# STM32F767ZI_eval_0.net
KiCad netlist of a schematic drawn in EAGLE
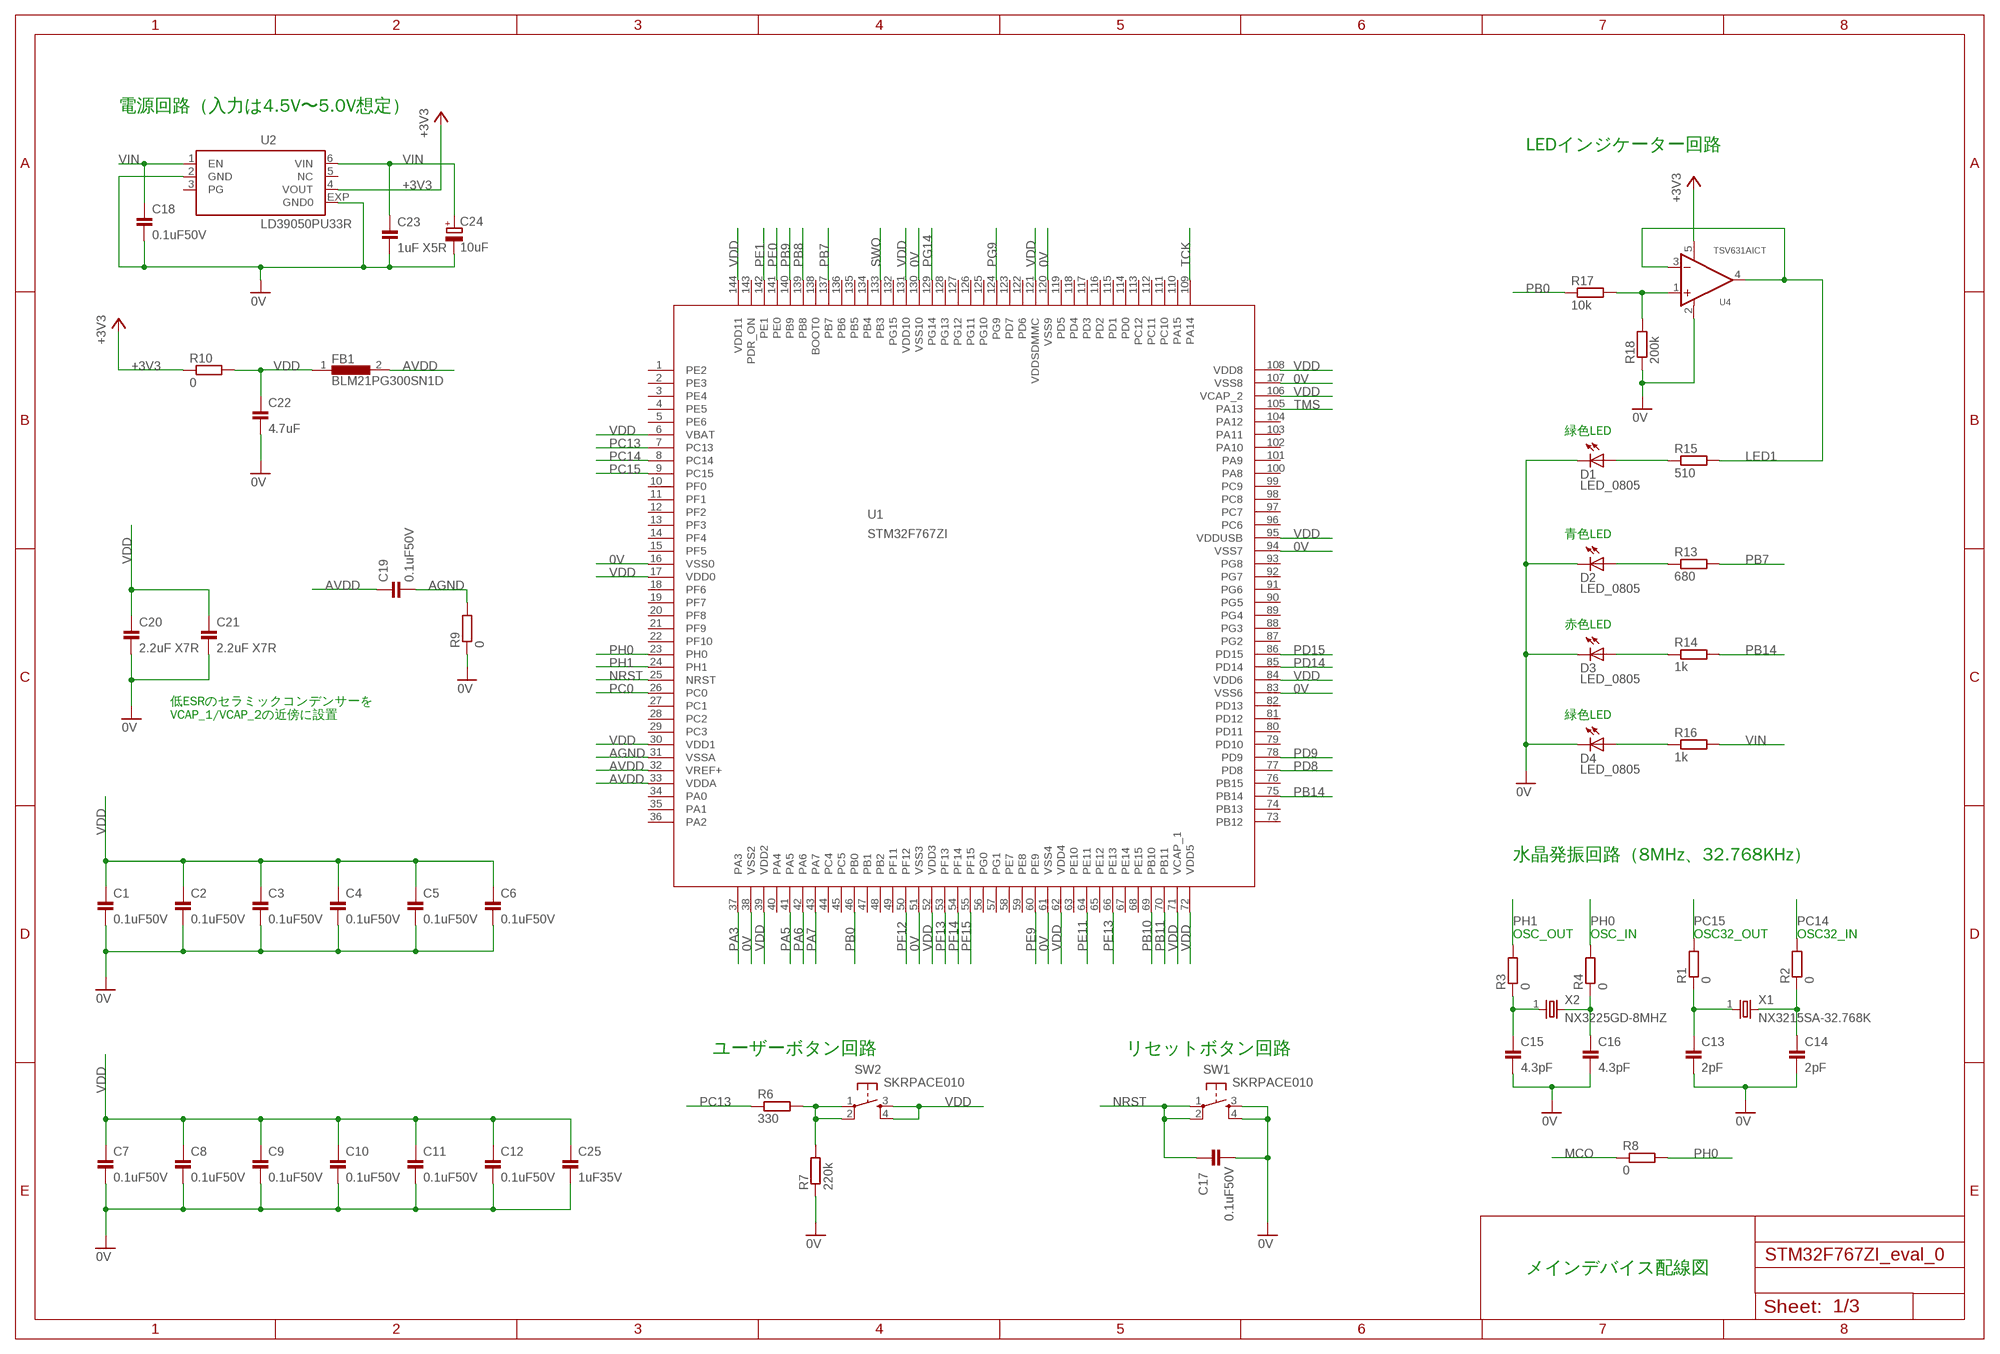
[diagram p0: schematic, sheet 1]
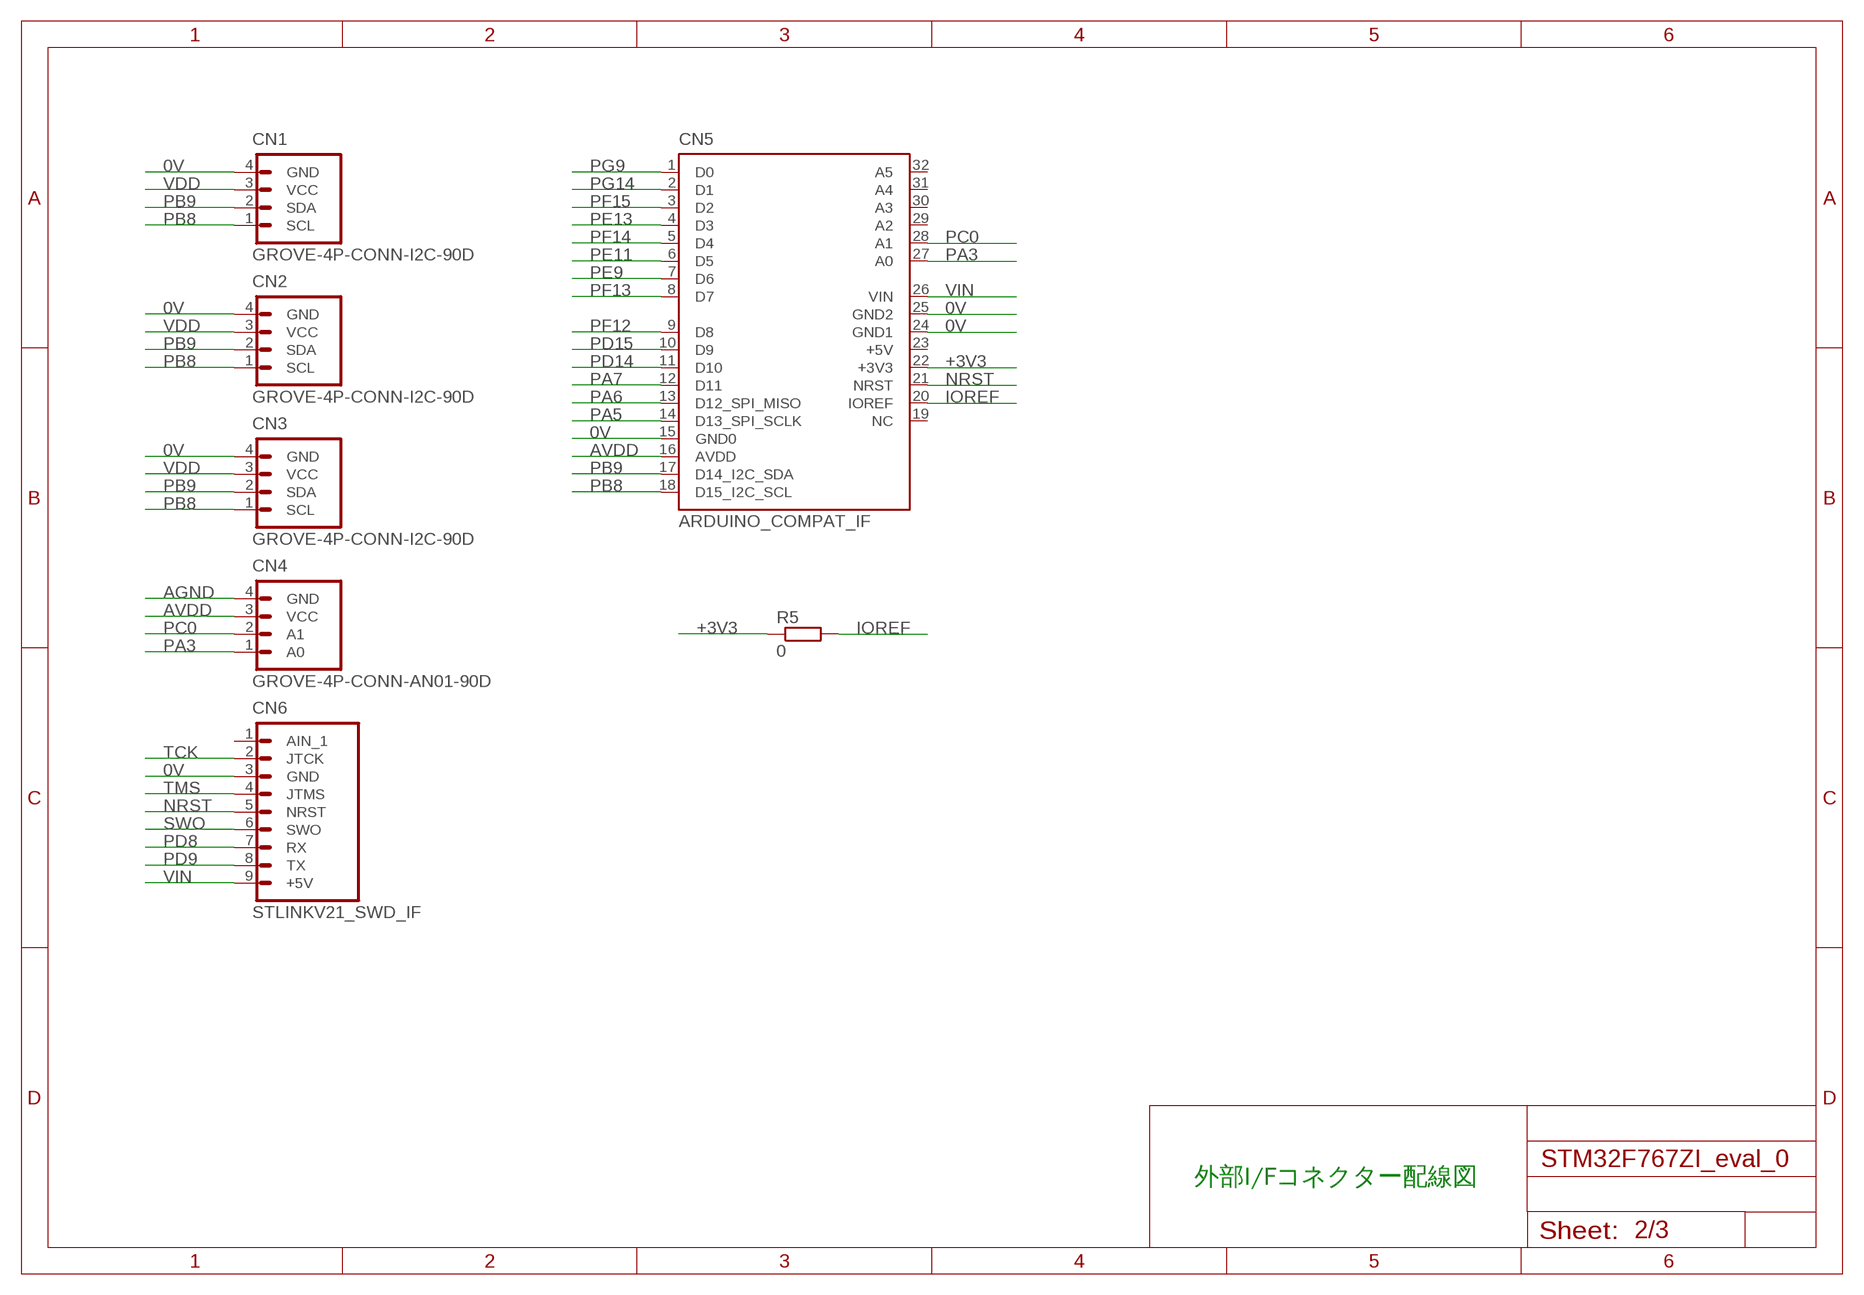
[diagram p1: schematic, sheet 2]
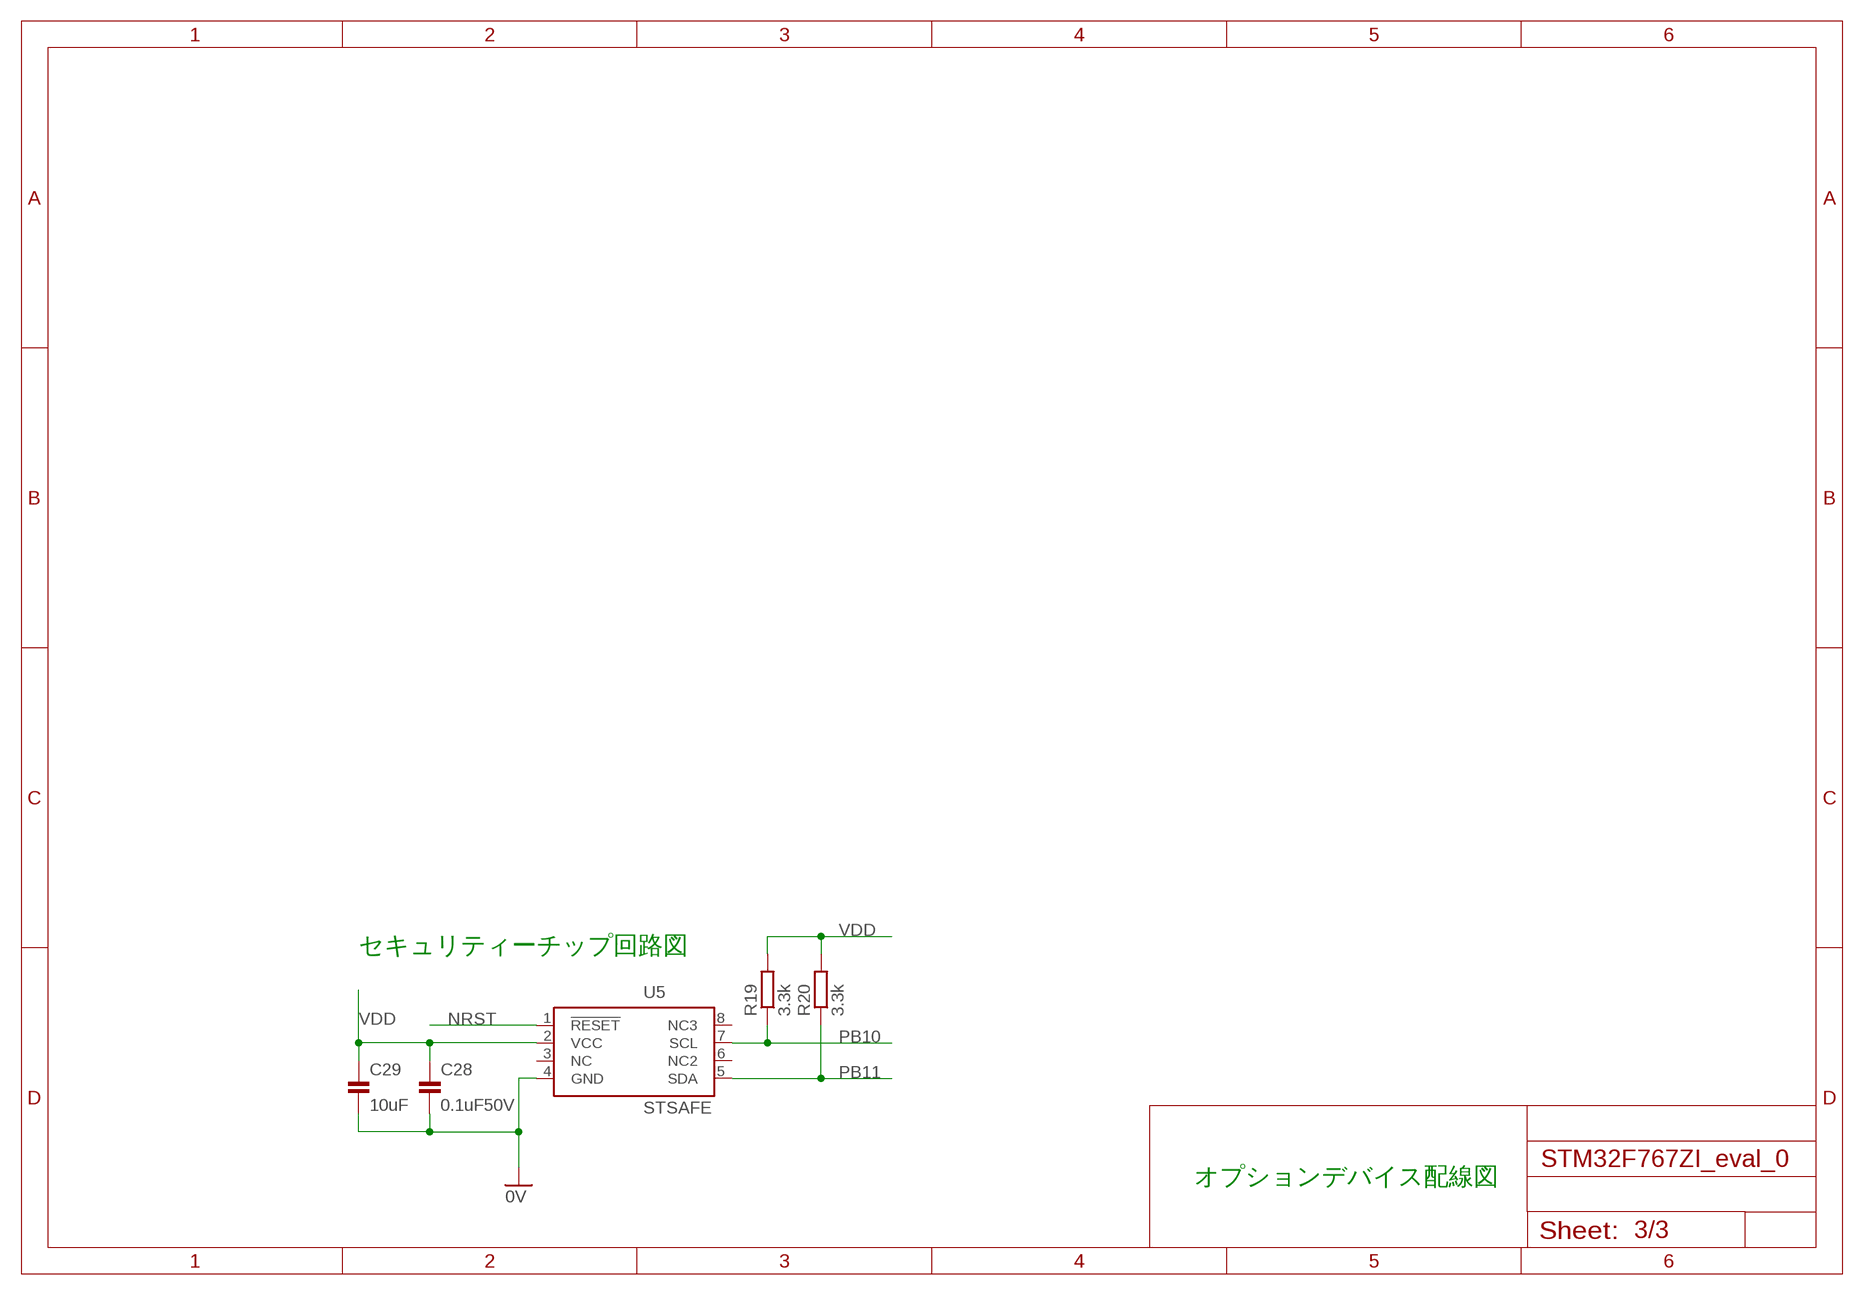
[diagram p2: schematic, sheet 3]

(export (version "E")
  (design (tool "Eeschema 10.0.6"))
  (components
    (comp (ref "C28")
      (value "0.1uF50V")
      (footprint "eagle-import:SMD_1608_DEV")
      (libsource (lib "eagle-import") (part "CAP_0603_DEV"))
    )
    (comp (ref "C29")
      (value "10uF")
      (footprint "eagle-import:SMD_2012_DEV")
      (libsource (lib "eagle-import") (part "CAP_0805_DEV"))
    )
    (comp (ref "R19")
      (value "3.3k")
      (footprint "eagle-import:SMD_1608_DEV")
      (libsource (lib "eagle-import") (part "RESISTOR_0603_DEV"))
    )
    (comp (ref "R20")
      (value "3.3k")
      (footprint "eagle-import:SMD_1608_DEV")
      (libsource (lib "eagle-import") (part "RESISTOR_0603_DEV"))
    )
    (comp (ref "U5")
      (value "STSAFE")
      (footprint "eagle-import:SO8")
      (libsource (lib "eagle-import") (part "STSAFE"))
    )
    (comp (ref "CN1")
      (value "GROVE-4P-CONN-I2C-90D")
      (footprint "eagle-import:GROVE-4P-90D")
      (libsource (lib "eagle-import") (part "GROVE-4P-CONN-I2C-90D"))
    )
    (comp (ref "CN2")
      (value "GROVE-4P-CONN-I2C-90D")
      (footprint "eagle-import:GROVE-4P-90D")
      (libsource (lib "eagle-import") (part "GROVE-4P-CONN-I2C-90D"))
    )
    (comp (ref "CN3")
      (value "GROVE-4P-CONN-I2C-90D")
      (footprint "eagle-import:GROVE-4P-90D")
      (libsource (lib "eagle-import") (part "GROVE-4P-CONN-I2C-90D"))
    )
    (comp (ref "CN4")
      (value "GROVE-4P-CONN-AN01-90D")
      (footprint "eagle-import:GROVE-4P-90D")
      (libsource (lib "eagle-import") (part "GROVE-4P-CONN-AN01-90D"))
    )
    (comp (ref "CN5")
      (value "ARDUINO_COMPAT_IF")
      (footprint "eagle-import:ARDUINO_COMPAT_IF")
      (libsource (lib "eagle-import") (part "ARDUINO_COMPAT_IF"))
    )
    (comp (ref "CN6")
      (value "STLINKV21_SWD_IF")
      (footprint "eagle-import:STLINKV21_SWD_H6")
      (libsource (lib "eagle-import") (part "STLINKV21_SWD_IF"))
    )
    (comp (ref "R5")
      (value "0")
      (footprint "eagle-import:SMD_1608_DEV")
      (libsource (lib "eagle-import") (part "RESISTOR_0603_DEV"))
    )
    (comp (ref "C1")
      (value "0.1uF50V")
      (footprint "eagle-import:SMD_1608_DEV")
      (libsource (lib "eagle-import") (part "CAP_0603_DEV"))
    )
    (comp (ref "C2")
      (value "0.1uF50V")
      (footprint "eagle-import:SMD_1608_DEV")
      (libsource (lib "eagle-import") (part "CAP_0603_DEV"))
    )
    (comp (ref "C3")
      (value "0.1uF50V")
      (footprint "eagle-import:SMD_1608_DEV")
      (libsource (lib "eagle-import") (part "CAP_0603_DEV"))
    )
    (comp (ref "C4")
      (value "0.1uF50V")
      (footprint "eagle-import:SMD_1608_DEV")
      (libsource (lib "eagle-import") (part "CAP_0603_DEV"))
    )
    (comp (ref "C5")
      (value "0.1uF50V")
      (footprint "eagle-import:SMD_1608_DEV")
      (libsource (lib "eagle-import") (part "CAP_0603_DEV"))
    )
    (comp (ref "C6")
      (value "0.1uF50V")
      (footprint "eagle-import:SMD_1608_DEV")
      (libsource (lib "eagle-import") (part "CAP_0603_DEV"))
    )
    (comp (ref "C7")
      (value "0.1uF50V")
      (footprint "eagle-import:SMD_1608_DEV")
      (libsource (lib "eagle-import") (part "CAP_0603_DEV"))
    )
    (comp (ref "C8")
      (value "0.1uF50V")
      (footprint "eagle-import:SMD_1608_DEV")
      (libsource (lib "eagle-import") (part "CAP_0603_DEV"))
    )
    (comp (ref "C9")
      (value "0.1uF50V")
      (footprint "eagle-import:SMD_1608_DEV")
      (libsource (lib "eagle-import") (part "CAP_0603_DEV"))
    )
    (comp (ref "C10")
      (value "0.1uF50V")
      (footprint "eagle-import:SMD_1608_DEV")
      (libsource (lib "eagle-import") (part "CAP_0603_DEV"))
    )
    (comp (ref "C11")
      (value "0.1uF50V")
      (footprint "eagle-import:SMD_1608_DEV")
      (libsource (lib "eagle-import") (part "CAP_0603_DEV"))
    )
    (comp (ref "C12")
      (value "0.1uF50V")
      (footprint "eagle-import:SMD_1608_DEV")
      (libsource (lib "eagle-import") (part "CAP_0603_DEV"))
    )
    (comp (ref "C13")
      (value "2pF")
      (footprint "eagle-import:SMD_1608_DEV")
      (libsource (lib "eagle-import") (part "CAP_0603_DEV"))
    )
    (comp (ref "C14")
      (value "2pF")
      (footprint "eagle-import:SMD_1608_DEV")
      (libsource (lib "eagle-import") (part "CAP_0603_DEV"))
    )
    (comp (ref "C15")
      (value "4.3pF")
      (footprint "eagle-import:SMD_1608_DEV")
      (libsource (lib "eagle-import") (part "CAP_0603_DEV"))
    )
    (comp (ref "C16")
      (value "4.3pF")
      (footprint "eagle-import:SMD_1608_DEV")
      (libsource (lib "eagle-import") (part "CAP_0603_DEV"))
    )
    (comp (ref "C17")
      (value "0.1uF50V")
      (footprint "eagle-import:SMD_1608_DEV")
      (libsource (lib "eagle-import") (part "CAP_0603_DEV"))
    )
    (comp (ref "C18")
      (value "0.1uF50V")
      (footprint "eagle-import:SMD_1608_DEV")
      (libsource (lib "eagle-import") (part "CAP_0603_DEV"))
    )
    (comp (ref "C19")
      (value "0.1uF50V")
      (footprint "eagle-import:SMD_1608_DEV")
      (libsource (lib "eagle-import") (part "CAP_0603_DEV"))
    )
    (comp (ref "C20")
      (value "2.2uF X7R")
      (footprint "eagle-import:SMD_1608_DEV")
      (libsource (lib "eagle-import") (part "CAP_0603_DEV"))
    )
    (comp (ref "C21")
      (value "2.2uF X7R")
      (footprint "eagle-import:SMD_1608_DEV")
      (libsource (lib "eagle-import") (part "CAP_0603_DEV"))
    )
    (comp (ref "C22")
      (value "4.7uF")
      (footprint "eagle-import:SMD_1608_DEV")
      (libsource (lib "eagle-import") (part "CAP_0603_DEV"))
    )
    (comp (ref "C23")
      (value "1uF X5R")
      (footprint "eagle-import:SMD_1608_DEV")
      (libsource (lib "eagle-import") (part "CAP_0603_DEV"))
    )
    (comp (ref "C24")
      (value "10uF")
      (footprint "eagle-import:C1210_TPST_DEV")
      (libsource (lib "eagle-import") (part "TPST106K016R0800_"))
    )
    (comp (ref "C25")
      (value "1uF35V")
      (footprint "eagle-import:SMD_1608_DEV")
      (libsource (lib "eagle-import") (part "CAP_0603_DEV"))
    )
    (comp (ref "D1")
      (value "LED_0805")
      (footprint "eagle-import:CHIPLED_0805")
      (libsource (lib "eagle-import") (part "LED_0805"))
    )
    (comp (ref "D2")
      (value "LED_0805")
      (footprint "eagle-import:CHIPLED_0805")
      (libsource (lib "eagle-import") (part "LED_0805"))
    )
    (comp (ref "D3")
      (value "LED_0805")
      (footprint "eagle-import:CHIPLED_0805")
      (libsource (lib "eagle-import") (part "LED_0805"))
    )
    (comp (ref "D4")
      (value "LED_0805")
      (footprint "eagle-import:CHIPLED_0805")
      (libsource (lib "eagle-import") (part "LED_0805"))
    )
    (comp (ref "FB1")
      (value "BLM21PG300SN1D")
      (footprint "eagle-import:SMD_2012_DEV")
      (libsource (lib "eagle-import") (part "BLM21PG300SN1D"))
    )
    (comp (ref "R1")
      (value "0")
      (footprint "eagle-import:SMD_1608_DEV")
      (libsource (lib "eagle-import") (part "RESISTOR_0603_DEV"))
    )
    (comp (ref "R2")
      (value "0")
      (footprint "eagle-import:SMD_1608_DEV")
      (libsource (lib "eagle-import") (part "RESISTOR_0603_DEV"))
    )
    (comp (ref "R3")
      (value "0")
      (footprint "eagle-import:SMD_1608_DEV")
      (libsource (lib "eagle-import") (part "RESISTOR_0603_DEV"))
    )
    (comp (ref "R4")
      (value "0")
      (footprint "eagle-import:SMD_1608_DEV")
      (libsource (lib "eagle-import") (part "RESISTOR_0603_DEV"))
    )
    (comp (ref "R6")
      (value "330")
      (footprint "eagle-import:SMD_1608_DEV")
      (libsource (lib "eagle-import") (part "RESISTOR_0603_DEV"))
    )
    (comp (ref "R7")
      (value "220k")
      (footprint "eagle-import:SMD_1608_DEV")
      (libsource (lib "eagle-import") (part "RESISTOR_0603_DEV"))
    )
    (comp (ref "R8")
      (value "0")
      (footprint "eagle-import:SMD_1608_DEV")
      (libsource (lib "eagle-import") (part "RESISTOR_0603_DEV"))
    )
    (comp (ref "R9")
      (value "0")
      (footprint "eagle-import:SMD_1608_DEV")
      (libsource (lib "eagle-import") (part "RESISTOR_0603_DEV"))
    )
    (comp (ref "R10")
      (value "0")
      (footprint "eagle-import:SMD_1608_DEV")
      (libsource (lib "eagle-import") (part "RESISTOR_0603_DEV"))
    )
    (comp (ref "R13")
      (value "680")
      (footprint "eagle-import:SMD_1608_DEV")
      (libsource (lib "eagle-import") (part "RESISTOR_0603_DEV"))
    )
    (comp (ref "R14")
      (value "1k")
      (footprint "eagle-import:SMD_1608_DEV")
      (libsource (lib "eagle-import") (part "RESISTOR_0603_DEV"))
    )
    (comp (ref "R15")
      (value "510")
      (footprint "eagle-import:SMD_1608_DEV")
      (libsource (lib "eagle-import") (part "RESISTOR_0603_DEV"))
    )
    (comp (ref "R16")
      (value "1k")
      (footprint "eagle-import:SMD_1608_DEV")
      (libsource (lib "eagle-import") (part "RESISTOR_0603_DEV"))
    )
    (comp (ref "R17")
      (value "10k")
      (footprint "eagle-import:SMD_1608_DEV")
      (libsource (lib "eagle-import") (part "RESISTOR_0603_DEV"))
    )
    (comp (ref "R18")
      (value "200k")
      (footprint "eagle-import:SMD_1608_DEV")
      (libsource (lib "eagle-import") (part "RESISTOR_0603_DEV"))
    )
    (comp (ref "SW1")
      (value "SKRPACE010")
      (footprint "eagle-import:SKRPACE010")
      (libsource (lib "eagle-import") (part "SKRPACE010"))
    )
    (comp (ref "SW2")
      (value "SKRPACE010")
      (footprint "eagle-import:SKRPACE010")
      (libsource (lib "eagle-import") (part "SKRPACE010"))
    )
    (comp (ref "U1")
      (value "STM32F767ZI")
      (footprint "eagle-import:LQFP144")
      (libsource (lib "eagle-import") (part "STM32F767ZI"))
    )
    (comp (ref "U2")
      (value "LD39050PU33R")
      (footprint "eagle-import:DFN6-3X3")
      (libsource (lib "eagle-import") (part "LD39050PU33R"))
    )
    (comp (ref "U4")
      (value "TSV631AICT")
      (footprint "eagle-import:SC-70-5")
      (libsource (lib "eagle-import") (part "TSV631AICT"))
    )
    (comp (ref "X1")
      (value "NX3215SA-32.768K")
      (footprint "eagle-import:NX3215")
      (libsource (lib "eagle-import") (part "NX3215SA-32.768K"))
    )
    (comp (ref "X2")
      (value "NX3225GD-8MHZ")
      (footprint "eagle-import:NX3225")
      (libsource (lib "eagle-import") (part "NX3225GD-8MHZ"))
    )
  )
  (nets
    (net (code "1") (name "+3V3") (class "Default")
      (node (ref "CN5") (pin "22") (pinfunction "+3V3_22") (pintype "passive"))
      (node (ref "R10") (pin "1") (pinfunction "1_1") (pintype "passive"))
      (node (ref "R5") (pin "1") (pinfunction "1_1") (pintype "passive"))
      (node (ref "U2") (pin "4") (pinfunction "VOUT_4") (pintype "passive"))
      (node (ref "U4") (pin "5") (pinfunction "V+_5") (pintype "passive"))
    )
    (net (code "2") (name "0V") (class "Default")
      (node (ref "C1") (pin "2") (pinfunction "2_2") (pintype "passive"))
      (node (ref "C10") (pin "2") (pinfunction "2_2") (pintype "passive"))
      (node (ref "C11") (pin "2") (pinfunction "2_2") (pintype "passive"))
      (node (ref "C12") (pin "2") (pinfunction "2_2") (pintype "passive"))
      (node (ref "C13") (pin "2") (pinfunction "2_2") (pintype "passive"))
      (node (ref "C14") (pin "2") (pinfunction "2_2") (pintype "passive"))
      (node (ref "C15") (pin "2") (pinfunction "2_2") (pintype "passive"))
      (node (ref "C16") (pin "2") (pinfunction "2_2") (pintype "passive"))
      (node (ref "C17") (pin "2") (pinfunction "2_2") (pintype "passive"))
      (node (ref "C18") (pin "2") (pinfunction "2_2") (pintype "passive"))
      (node (ref "C2") (pin "2") (pinfunction "2_2") (pintype "passive"))
      (node (ref "C20") (pin "2") (pinfunction "2_2") (pintype "passive"))
      (node (ref "C21") (pin "2") (pinfunction "2_2") (pintype "passive"))
      (node (ref "C22") (pin "2") (pinfunction "2_2") (pintype "passive"))
      (node (ref "C23") (pin "2") (pinfunction "2_2") (pintype "passive"))
      (node (ref "C24") (pin "2") (pinfunction "-_2") (pintype "passive"))
      (node (ref "C25") (pin "2") (pinfunction "2_2") (pintype "passive"))
      (node (ref "C28") (pin "2") (pinfunction "2_2") (pintype "passive"))
      (node (ref "C29") (pin "2") (pinfunction "2_2") (pintype "passive"))
      (node (ref "C3") (pin "2") (pinfunction "2_2") (pintype "passive"))
      (node (ref "C4") (pin "2") (pinfunction "2_2") (pintype "passive"))
      (node (ref "C5") (pin "2") (pinfunction "2_2") (pintype "passive"))
      (node (ref "C6") (pin "2") (pinfunction "2_2") (pintype "passive"))
      (node (ref "C7") (pin "2") (pinfunction "2_2") (pintype "passive"))
      (node (ref "C8") (pin "2") (pinfunction "2_2") (pintype "passive"))
      (node (ref "C9") (pin "2") (pinfunction "2_2") (pintype "passive"))
      (node (ref "CN1") (pin "4") (pinfunction "GND_4") (pintype "passive"))
      (node (ref "CN2") (pin "4") (pinfunction "GND_4") (pintype "passive"))
      (node (ref "CN3") (pin "4") (pinfunction "GND_4") (pintype "passive"))
      (node (ref "CN5") (pin "15") (pinfunction "GND0_15") (pintype "passive"))
      (node (ref "CN5") (pin "24") (pinfunction "GND1_24") (pintype "passive"))
      (node (ref "CN5") (pin "25") (pinfunction "GND2_25") (pintype "passive"))
      (node (ref "CN6") (pin "3") (pinfunction "GND_3") (pintype "passive"))
      (node (ref "D1") (pin "C") (pinfunction "C_C") (pintype "passive"))
      (node (ref "D2") (pin "C") (pinfunction "C_C") (pintype "passive"))
      (node (ref "D3") (pin "C") (pinfunction "C_C") (pintype "passive"))
      (node (ref "D4") (pin "C") (pinfunction "C_C") (pintype "passive"))
      (node (ref "R18") (pin "1") (pinfunction "1_1") (pintype "passive"))
      (node (ref "R7") (pin "1") (pinfunction "1_1") (pintype "passive"))
      (node (ref "R9") (pin "1") (pinfunction "1_1") (pintype "passive"))
      (node (ref "SW1") (pin "3") (pinfunction "S_3") (pintype "passive"))
      (node (ref "SW1") (pin "4") (pinfunction "S1_4") (pintype "passive"))
      (node (ref "U1") (pin "107") (pinfunction "VSS8_107") (pintype "passive"))
      (node (ref "U1") (pin "120") (pinfunction "VSS9_120") (pintype "passive"))
      (node (ref "U1") (pin "130") (pinfunction "VSS10_130") (pintype "passive"))
      (node (ref "U1") (pin "16") (pinfunction "VSS0_16") (pintype "passive"))
      (node (ref "U1") (pin "38") (pinfunction "VSS2_38") (pintype "passive"))
      (node (ref "U1") (pin "51") (pinfunction "VSS3_51") (pintype "bidirectional"))
      (node (ref "U1") (pin "61") (pinfunction "VSS4_61") (pintype "passive"))
      (node (ref "U1") (pin "83") (pinfunction "VSS6_83") (pintype "passive"))
      (node (ref "U1") (pin "94") (pinfunction "VSS7_94") (pintype "passive"))
      (node (ref "U2") (pin "2") (pinfunction "GND_2") (pintype "passive"))
      (node (ref "U2") (pin "EXP") (pinfunction "GND0_EXP") (pintype "passive"))
      (node (ref "U4") (pin "2") (pinfunction "V-_2") (pintype "passive"))
      (node (ref "U5") (pin "4") (pinfunction "GND_4") (pintype "passive"))
    )
    (net (code "3") (name "AGND") (class "Default")
      (node (ref "C19") (pin "2") (pinfunction "2_2") (pintype "passive"))
      (node (ref "CN4") (pin "4") (pinfunction "GND_4") (pintype "passive"))
      (node (ref "R9") (pin "2") (pinfunction "2_2") (pintype "passive"))
      (node (ref "U1") (pin "31") (pinfunction "VSSA_31") (pintype "passive"))
    )
    (net (code "4") (name "AVDD") (class "Default")
      (node (ref "C19") (pin "1") (pinfunction "1_1") (pintype "passive"))
      (node (ref "CN4") (pin "3") (pinfunction "VCC_3") (pintype "passive"))
      (node (ref "CN5") (pin "16") (pinfunction "AVDD_16") (pintype "passive"))
      (node (ref "FB1") (pin "2") (pinfunction "2_2") (pintype "passive"))
      (node (ref "U1") (pin "32") (pinfunction "VREF+_32") (pintype "passive"))
      (node (ref "U1") (pin "33") (pinfunction "VDDA_33") (pintype "passive"))
    )
    (net (code "5") (name "IOREF") (class "Default")
      (node (ref "CN5") (pin "20") (pinfunction "IOREF_20") (pintype "bidirectional"))
      (node (ref "R5") (pin "2") (pinfunction "2_2") (pintype "passive"))
    )
    (net (code "6") (name "LED1") (class "Default")
      (node (ref "R15") (pin "2") (pinfunction "2_2") (pintype "passive"))
      (node (ref "U4") (pin "3") (pinfunction "IN-_3") (pintype "input"))
      (node (ref "U4") (pin "4") (pinfunction "OUT_4") (pintype "output"))
    )
    (net (code "7") (name "MCO") (class "Default")
      (node (ref "R8") (pin "1") (pinfunction "1_1") (pintype "passive"))
    )
    (net (code "8") (name "NRST") (class "Default")
      (node (ref "C17") (pin "1") (pinfunction "1_1") (pintype "passive"))
      (node (ref "CN5") (pin "21") (pinfunction "NRST_21") (pintype "bidirectional"))
      (node (ref "CN6") (pin "5") (pinfunction "NRST_5") (pintype "bidirectional"))
      (node (ref "SW1") (pin "1") (pinfunction "P_1") (pintype "passive"))
      (node (ref "SW1") (pin "2") (pinfunction "P1_2") (pintype "passive"))
      (node (ref "U1") (pin "25") (pinfunction "NRST_25") (pintype "bidirectional"))
      (node (ref "U5") (pin "1") (pinfunction "~{RESET}_1") (pintype "bidirectional"))
    )
    (net (code "9") (name "Net-(C13-Pad1)") (class "Default")
      (node (ref "C13") (pin "1") (pinfunction "1_1") (pintype "passive"))
      (node (ref "R1") (pin "1") (pinfunction "1_1") (pintype "passive"))
      (node (ref "X1") (pin "1") (pinfunction "1_1") (pintype "passive"))
    )
    (net (code "10") (name "Net-(C14-Pad1)") (class "Default")
      (node (ref "C14") (pin "1") (pinfunction "1_1") (pintype "passive"))
      (node (ref "R2") (pin "1") (pinfunction "1_1") (pintype "passive"))
      (node (ref "X1") (pin "2") (pinfunction "2_2") (pintype "passive"))
    )
    (net (code "11") (name "Net-(C15-Pad1)") (class "Default")
      (node (ref "C15") (pin "1") (pinfunction "1_1") (pintype "passive"))
      (node (ref "R3") (pin "1") (pinfunction "1_1") (pintype "passive"))
      (node (ref "X2") (pin "1") (pinfunction "1_1") (pintype "passive"))
    )
    (net (code "12") (name "Net-(C16-Pad1)") (class "Default")
      (node (ref "C16") (pin "1") (pinfunction "1_1") (pintype "passive"))
      (node (ref "R4") (pin "1") (pinfunction "1_1") (pintype "passive"))
      (node (ref "X2") (pin "2") (pinfunction "2_2") (pintype "passive"))
    )
    (net (code "13") (name "Net-(D1-PadA)") (class "Default")
      (node (ref "D1") (pin "A") (pinfunction "A_A") (pintype "passive"))
      (node (ref "R15") (pin "1") (pinfunction "1_1") (pintype "passive"))
    )
    (net (code "14") (name "Net-(D2-PadA)") (class "Default")
      (node (ref "D2") (pin "A") (pinfunction "A_A") (pintype "passive"))
      (node (ref "R13") (pin "1") (pinfunction "1_1") (pintype "passive"))
    )
    (net (code "15") (name "Net-(D3-PadA)") (class "Default")
      (node (ref "D3") (pin "A") (pinfunction "A_A") (pintype "passive"))
      (node (ref "R14") (pin "1") (pinfunction "1_1") (pintype "passive"))
    )
    (net (code "16") (name "Net-(D4-PadA)") (class "Default")
      (node (ref "D4") (pin "A") (pinfunction "A_A") (pintype "passive"))
      (node (ref "R16") (pin "1") (pinfunction "1_1") (pintype "passive"))
    )
    (net (code "17") (name "Net-(SW2-P)") (class "Default")
      (node (ref "R6") (pin "2") (pinfunction "2_2") (pintype "passive"))
      (node (ref "R7") (pin "2") (pinfunction "2_2") (pintype "passive"))
      (node (ref "SW2") (pin "1") (pinfunction "P_1") (pintype "passive"))
      (node (ref "SW2") (pin "2") (pinfunction "P1_2") (pintype "passive"))
    )
    (net (code "18") (name "Net-(U4-IN+)") (class "Default")
      (node (ref "R17") (pin "2") (pinfunction "2_2") (pintype "passive"))
      (node (ref "R18") (pin "2") (pinfunction "2_2") (pintype "passive"))
      (node (ref "U4") (pin "1") (pinfunction "IN+_1") (pintype "input"))
    )
    (net (code "19") (name "PA3") (class "Default")
      (node (ref "CN4") (pin "1") (pinfunction "A0_1") (pintype "bidirectional"))
      (node (ref "CN5") (pin "27") (pinfunction "A0_27") (pintype "bidirectional"))
      (node (ref "U1") (pin "37") (pinfunction "PA3_37") (pintype "bidirectional"))
    )
    (net (code "20") (name "PA5") (class "Default")
      (node (ref "CN5") (pin "14") (pinfunction "D13_SPI_SCLK_14") (pintype "bidirectional"))
      (node (ref "U1") (pin "41") (pinfunction "PA5_41") (pintype "bidirectional"))
    )
    (net (code "21") (name "PA6") (class "Default")
      (node (ref "CN5") (pin "13") (pinfunction "D12_SPI_MISO_13") (pintype "bidirectional"))
      (node (ref "U1") (pin "42") (pinfunction "PA6_42") (pintype "bidirectional"))
    )
    (net (code "22") (name "PA7") (class "Default")
      (node (ref "CN5") (pin "12") (pinfunction "D11_12") (pintype "bidirectional"))
      (node (ref "U1") (pin "43") (pinfunction "PA7_43") (pintype "bidirectional"))
    )
    (net (code "23") (name "PB0") (class "Default")
      (node (ref "R17") (pin "1") (pinfunction "1_1") (pintype "passive"))
      (node (ref "U1") (pin "46") (pinfunction "PB0_46") (pintype "bidirectional"))
    )
    (net (code "24") (name "PB7") (class "Default")
      (node (ref "R13") (pin "2") (pinfunction "2_2") (pintype "passive"))
      (node (ref "U1") (pin "137") (pinfunction "PB7_137") (pintype "bidirectional"))
    )
    (net (code "25") (name "PB8") (class "Default")
      (node (ref "CN1") (pin "1") (pinfunction "SCL_1") (pintype "bidirectional"))
      (node (ref "CN2") (pin "1") (pinfunction "SCL_1") (pintype "bidirectional"))
      (node (ref "CN3") (pin "1") (pinfunction "SCL_1") (pintype "bidirectional"))
      (node (ref "CN5") (pin "18") (pinfunction "D15_I2C_SCL_18") (pintype "passive"))
      (node (ref "U1") (pin "139") (pinfunction "PB8_139") (pintype "bidirectional"))
    )
    (net (code "26") (name "PB9") (class "Default")
      (node (ref "CN1") (pin "2") (pinfunction "SDA_2") (pintype "bidirectional"))
      (node (ref "CN2") (pin "2") (pinfunction "SDA_2") (pintype "bidirectional"))
      (node (ref "CN3") (pin "2") (pinfunction "SDA_2") (pintype "bidirectional"))
      (node (ref "CN5") (pin "17") (pinfunction "D14_I2C_SDA_17") (pintype "passive"))
      (node (ref "U1") (pin "140") (pinfunction "PB9_140") (pintype "bidirectional"))
    )
    (net (code "27") (name "PB10") (class "Default")
      (node (ref "R19") (pin "1") (pinfunction "1_1") (pintype "passive"))
      (node (ref "U1") (pin "69") (pinfunction "PB10_69") (pintype "bidirectional"))
      (node (ref "U5") (pin "7") (pinfunction "SCL_7") (pintype "bidirectional"))
    )
    (net (code "28") (name "PB11") (class "Default")
      (node (ref "R20") (pin "1") (pinfunction "1_1") (pintype "passive"))
      (node (ref "U1") (pin "70") (pinfunction "PB11_70") (pintype "bidirectional"))
      (node (ref "U5") (pin "5") (pinfunction "SDA_5") (pintype "bidirectional"))
    )
    (net (code "29") (name "PB14") (class "Default")
      (node (ref "R14") (pin "2") (pinfunction "2_2") (pintype "passive"))
      (node (ref "U1") (pin "75") (pinfunction "PB14_75") (pintype "bidirectional"))
    )
    (net (code "30") (name "PC0") (class "Default")
      (node (ref "CN4") (pin "2") (pinfunction "A1_2") (pintype "bidirectional"))
      (node (ref "CN5") (pin "28") (pinfunction "A1_28") (pintype "bidirectional"))
      (node (ref "U1") (pin "26") (pinfunction "PC0_26") (pintype "bidirectional"))
    )
    (net (code "31") (name "PC13") (class "Default")
      (node (ref "R6") (pin "1") (pinfunction "1_1") (pintype "passive"))
      (node (ref "U1") (pin "7") (pinfunction "PC13_7") (pintype "bidirectional"))
    )
    (net (code "32") (name "PC14") (class "Default")
      (node (ref "R2") (pin "2") (pinfunction "2_2") (pintype "passive"))
      (node (ref "U1") (pin "8") (pinfunction "PC14_8") (pintype "bidirectional"))
    )
    (net (code "33") (name "PC15") (class "Default")
      (node (ref "R1") (pin "2") (pinfunction "2_2") (pintype "passive"))
      (node (ref "U1") (pin "9") (pinfunction "PC15_9") (pintype "bidirectional"))
    )
    (net (code "34") (name "PD8") (class "Default")
      (node (ref "CN6") (pin "7") (pinfunction "RX_7") (pintype "bidirectional"))
      (node (ref "U1") (pin "77") (pinfunction "PD8_77") (pintype "bidirectional"))
    )
    (net (code "35") (name "PD9") (class "Default")
      (node (ref "CN6") (pin "8") (pinfunction "TX_8") (pintype "bidirectional"))
      (node (ref "U1") (pin "78") (pinfunction "PD9_78") (pintype "bidirectional"))
    )
    (net (code "36") (name "PD14") (class "Default")
      (node (ref "CN5") (pin "11") (pinfunction "D10_11") (pintype "bidirectional"))
      (node (ref "U1") (pin "85") (pinfunction "PD14_85") (pintype "bidirectional"))
    )
    (net (code "37") (name "PD15") (class "Default")
      (node (ref "CN5") (pin "10") (pinfunction "D9_10") (pintype "bidirectional"))
      (node (ref "U1") (pin "86") (pinfunction "PD15_86") (pintype "bidirectional"))
    )
    (net (code "38") (name "PE0") (class "Default")
      (node (ref "U1") (pin "141") (pinfunction "PE0_141") (pintype "bidirectional"))
    )
    (net (code "39") (name "PE1") (class "Default")
      (node (ref "U1") (pin "142") (pinfunction "PE1_142") (pintype "bidirectional"))
    )
    (net (code "40") (name "PE9") (class "Default")
      (node (ref "CN5") (pin "7") (pinfunction "D6_7") (pintype "bidirectional"))
      (node (ref "U1") (pin "60") (pinfunction "PE9_60") (pintype "bidirectional"))
    )
    (net (code "41") (name "PE11") (class "Default")
      (node (ref "CN5") (pin "6") (pinfunction "D5_6") (pintype "bidirectional"))
      (node (ref "U1") (pin "64") (pinfunction "PE11_64") (pintype "bidirectional"))
    )
    (net (code "42") (name "PE13") (class "Default")
      (node (ref "CN5") (pin "4") (pinfunction "D3_4") (pintype "bidirectional"))
      (node (ref "U1") (pin "66") (pinfunction "PE13_66") (pintype "bidirectional"))
    )
    (net (code "43") (name "PF12") (class "Default")
      (node (ref "CN5") (pin "9") (pinfunction "D8_9") (pintype "bidirectional"))
      (node (ref "U1") (pin "50") (pinfunction "PF12_50") (pintype "bidirectional"))
    )
    (net (code "44") (name "PF13") (class "Default")
      (node (ref "CN5") (pin "8") (pinfunction "D7_8") (pintype "bidirectional"))
      (node (ref "U1") (pin "53") (pinfunction "PF13_53") (pintype "bidirectional"))
    )
    (net (code "45") (name "PF14") (class "Default")
      (node (ref "CN5") (pin "5") (pinfunction "D4_5") (pintype "bidirectional"))
      (node (ref "U1") (pin "54") (pinfunction "PF14_54") (pintype "bidirectional"))
    )
    (net (code "46") (name "PF15") (class "Default")
      (node (ref "CN5") (pin "3") (pinfunction "D2_3") (pintype "bidirectional"))
      (node (ref "U1") (pin "55") (pinfunction "PF15_55") (pintype "bidirectional"))
    )
    (net (code "47") (name "PG9") (class "Default")
      (node (ref "CN5") (pin "1") (pinfunction "D0_1") (pintype "bidirectional"))
      (node (ref "U1") (pin "124") (pinfunction "PG9_124") (pintype "bidirectional"))
    )
    (net (code "48") (name "PG14") (class "Default")
      (node (ref "CN5") (pin "2") (pinfunction "D1_2") (pintype "bidirectional"))
      (node (ref "U1") (pin "129") (pinfunction "PG14_129") (pintype "bidirectional"))
    )
    (net (code "49") (name "PH0") (class "Default")
      (node (ref "R4") (pin "2") (pinfunction "2_2") (pintype "passive"))
      (node (ref "R8") (pin "2") (pinfunction "2_2") (pintype "passive"))
      (node (ref "U1") (pin "23") (pinfunction "PH0_23") (pintype "bidirectional"))
    )
    (net (code "50") (name "PH1") (class "Default")
      (node (ref "R3") (pin "2") (pinfunction "2_2") (pintype "passive"))
      (node (ref "U1") (pin "24") (pinfunction "PH1_24") (pintype "bidirectional"))
    )
    (net (code "51") (name "SWO") (class "Default")
      (node (ref "CN6") (pin "6") (pinfunction "SWO_6") (pintype "bidirectional"))
      (node (ref "U1") (pin "133") (pinfunction "PB3_133") (pintype "bidirectional"))
    )
    (net (code "52") (name "TCK") (class "Default")
      (node (ref "CN6") (pin "2") (pinfunction "JTCK_2") (pintype "bidirectional"))
      (node (ref "U1") (pin "109") (pinfunction "PA14_109") (pintype "bidirectional"))
    )
    (net (code "53") (name "TMS") (class "Default")
      (node (ref "CN6") (pin "4") (pinfunction "JTMS_4") (pintype "bidirectional"))
      (node (ref "U1") (pin "105") (pinfunction "PA13_105") (pintype "bidirectional"))
    )
    (net (code "54") (name "VDD") (class "Default")
      (node (ref "C1") (pin "1") (pinfunction "1_1") (pintype "passive"))
      (node (ref "C10") (pin "1") (pinfunction "1_1") (pintype "passive"))
      (node (ref "C11") (pin "1") (pinfunction "1_1") (pintype "passive"))
      (node (ref "C12") (pin "1") (pinfunction "1_1") (pintype "passive"))
      (node (ref "C2") (pin "1") (pinfunction "1_1") (pintype "passive"))
      (node (ref "C20") (pin "1") (pinfunction "1_1") (pintype "passive"))
      (node (ref "C21") (pin "1") (pinfunction "1_1") (pintype "passive"))
      (node (ref "C22") (pin "1") (pinfunction "1_1") (pintype "passive"))
      (node (ref "C25") (pin "1") (pinfunction "1_1") (pintype "passive"))
      (node (ref "C28") (pin "1") (pinfunction "1_1") (pintype "passive"))
      (node (ref "C29") (pin "1") (pinfunction "1_1") (pintype "passive"))
      (node (ref "C3") (pin "1") (pinfunction "1_1") (pintype "passive"))
      (node (ref "C4") (pin "1") (pinfunction "1_1") (pintype "passive"))
      (node (ref "C5") (pin "1") (pinfunction "1_1") (pintype "passive"))
      (node (ref "C6") (pin "1") (pinfunction "1_1") (pintype "passive"))
      (node (ref "C7") (pin "1") (pinfunction "1_1") (pintype "passive"))
      (node (ref "C8") (pin "1") (pinfunction "1_1") (pintype "passive"))
      (node (ref "C9") (pin "1") (pinfunction "1_1") (pintype "passive"))
      (node (ref "CN1") (pin "3") (pinfunction "VCC_3") (pintype "passive"))
      (node (ref "CN2") (pin "3") (pinfunction "VCC_3") (pintype "passive"))
      (node (ref "CN3") (pin "3") (pinfunction "VCC_3") (pintype "passive"))
      (node (ref "FB1") (pin "1") (pinfunction "1_1") (pintype "passive"))
      (node (ref "R10") (pin "2") (pinfunction "2_2") (pintype "passive"))
      (node (ref "R19") (pin "2") (pinfunction "2_2") (pintype "passive"))
      (node (ref "R20") (pin "2") (pinfunction "2_2") (pintype "passive"))
      (node (ref "SW2") (pin "3") (pinfunction "S_3") (pintype "passive"))
      (node (ref "SW2") (pin "4") (pinfunction "S1_4") (pintype "passive"))
      (node (ref "U1") (pin "106") (pinfunction "VCAP_2_106") (pintype "passive"))
      (node (ref "U1") (pin "108") (pinfunction "VDD8_108") (pintype "passive"))
      (node (ref "U1") (pin "121") (pinfunction "VDDSDMMC_121") (pintype "passive"))
      (node (ref "U1") (pin "131") (pinfunction "VDD10_131") (pintype "passive"))
      (node (ref "U1") (pin "144") (pinfunction "VDD11_144") (pintype "passive"))
      (node (ref "U1") (pin "17") (pinfunction "VDD0_17") (pintype "passive"))
      (node (ref "U1") (pin "30") (pinfunction "VDD1_30") (pintype "passive"))
      (node (ref "U1") (pin "39") (pinfunction "VDD2_39") (pintype "passive"))
      (node (ref "U1") (pin "52") (pinfunction "VDD3_52") (pintype "passive"))
      (node (ref "U1") (pin "6") (pinfunction "VBAT_6") (pintype "passive"))
      (node (ref "U1") (pin "62") (pinfunction "VDD4_62") (pintype "passive"))
      (node (ref "U1") (pin "71") (pinfunction "VCAP_1_71") (pintype "passive"))
      (node (ref "U1") (pin "72") (pinfunction "VDD5_72") (pintype "passive"))
      (node (ref "U1") (pin "84") (pinfunction "VDD6_84") (pintype "passive"))
      (node (ref "U1") (pin "95") (pinfunction "VDDUSB_95") (pintype "passive"))
      (node (ref "U5") (pin "2") (pinfunction "VCC_2") (pintype "passive"))
    )
    (net (code "55") (name "VIN") (class "Default")
      (node (ref "C18") (pin "1") (pinfunction "1_1") (pintype "passive"))
      (node (ref "C23") (pin "1") (pinfunction "1_1") (pintype "passive"))
      (node (ref "C24") (pin "1") (pinfunction "+_1") (pintype "passive"))
      (node (ref "CN5") (pin "26") (pinfunction "VIN_26") (pintype "passive"))
      (node (ref "CN6") (pin "9") (pinfunction "+5V_9") (pintype "passive"))
      (node (ref "R16") (pin "2") (pinfunction "2_2") (pintype "passive"))
      (node (ref "U2") (pin "1") (pinfunction "EN_1") (pintype "bidirectional"))
      (node (ref "U2") (pin "6") (pinfunction "VIN_6") (pintype "passive"))
    )
    (net (code "56") (name "unconnected-(CN5-+5V-Pad23)") (class "Default")
      (node (ref "CN5") (pin "23") (pinfunction "+5V_23") (pintype "passive"))
    )
    (net (code "57") (name "unconnected-(CN5-A2-Pad29)") (class "Default")
      (node (ref "CN5") (pin "29") (pinfunction "A2_29") (pintype "bidirectional"))
    )
    (net (code "58") (name "unconnected-(CN5-A3-Pad30)") (class "Default")
      (node (ref "CN5") (pin "30") (pinfunction "A3_30") (pintype "bidirectional"))
    )
    (net (code "59") (name "unconnected-(CN5-A4-Pad31)") (class "Default")
      (node (ref "CN5") (pin "31") (pinfunction "A4_31") (pintype "bidirectional"))
    )
    (net (code "60") (name "unconnected-(CN5-A5-Pad32)") (class "Default")
      (node (ref "CN5") (pin "32") (pinfunction "A5_32") (pintype "bidirectional"))
    )
    (net (code "61") (name "unconnected-(CN5-NC-Pad19)") (class "Default")
      (node (ref "CN5") (pin "19") (pinfunction "NC_19") (pintype "no_connect"))
    )
    (net (code "62") (name "unconnected-(CN6-AIN_1-Pad1)") (class "Default")
      (node (ref "CN6") (pin "1") (pinfunction "AIN_1_1") (pintype "bidirectional"))
    )
    (net (code "63") (name "unconnected-(U1-BOOT0-Pad138)") (class "Default")
      (node (ref "U1") (pin "138") (pinfunction "BOOT0_138") (pintype "bidirectional"))
    )
    (net (code "64") (name "unconnected-(U1-PA0-Pad34)") (class "Default")
      (node (ref "U1") (pin "34") (pinfunction "PA0_34") (pintype "bidirectional"))
    )
    (net (code "65") (name "unconnected-(U1-PA1-Pad35)") (class "Default")
      (node (ref "U1") (pin "35") (pinfunction "PA1_35") (pintype "bidirectional"))
    )
    (net (code "66") (name "unconnected-(U1-PA2-Pad36)") (class "Default")
      (node (ref "U1") (pin "36") (pinfunction "PA2_36") (pintype "bidirectional"))
    )
    (net (code "67") (name "unconnected-(U1-PA4-Pad40)") (class "Default")
      (node (ref "U1") (pin "40") (pinfunction "PA4_40") (pintype "bidirectional"))
    )
    (net (code "68") (name "unconnected-(U1-PA8-Pad100)") (class "Default")
      (node (ref "U1") (pin "100") (pinfunction "PA8_100") (pintype "passive"))
    )
    (net (code "69") (name "unconnected-(U1-PA9-Pad101)") (class "Default")
      (node (ref "U1") (pin "101") (pinfunction "PA9_101") (pintype "passive"))
    )
    (net (code "70") (name "unconnected-(U1-PA10-Pad102)") (class "Default")
      (node (ref "U1") (pin "102") (pinfunction "PA10_102") (pintype "bidirectional"))
    )
    (net (code "71") (name "unconnected-(U1-PA11-Pad103)") (class "Default")
      (node (ref "U1") (pin "103") (pinfunction "PA11_103") (pintype "bidirectional"))
    )
    (net (code "72") (name "unconnected-(U1-PA12-Pad104)") (class "Default")
      (node (ref "U1") (pin "104") (pinfunction "PA12_104") (pintype "bidirectional"))
    )
    (net (code "73") (name "unconnected-(U1-PA15-Pad110)") (class "Default")
      (node (ref "U1") (pin "110") (pinfunction "PA15_110") (pintype "bidirectional"))
    )
    (net (code "74") (name "unconnected-(U1-PB1-Pad47)") (class "Default")
      (node (ref "U1") (pin "47") (pinfunction "PB1_47") (pintype "bidirectional"))
    )
    (net (code "75") (name "unconnected-(U1-PB2-Pad48)") (class "Default")
      (node (ref "U1") (pin "48") (pinfunction "PB2_48") (pintype "bidirectional"))
    )
    (net (code "76") (name "unconnected-(U1-PB4-Pad134)") (class "Default")
      (node (ref "U1") (pin "134") (pinfunction "PB4_134") (pintype "bidirectional"))
    )
    (net (code "77") (name "unconnected-(U1-PB5-Pad135)") (class "Default")
      (node (ref "U1") (pin "135") (pinfunction "PB5_135") (pintype "bidirectional"))
    )
    (net (code "78") (name "unconnected-(U1-PB6-Pad136)") (class "Default")
      (node (ref "U1") (pin "136") (pinfunction "PB6_136") (pintype "bidirectional"))
    )
    (net (code "79") (name "unconnected-(U1-PB12-Pad73)") (class "Default")
      (node (ref "U1") (pin "73") (pinfunction "PB12_73") (pintype "bidirectional"))
    )
    (net (code "80") (name "unconnected-(U1-PB13-Pad74)") (class "Default")
      (node (ref "U1") (pin "74") (pinfunction "PB13_74") (pintype "bidirectional"))
    )
    (net (code "81") (name "unconnected-(U1-PB15-Pad76)") (class "Default")
      (node (ref "U1") (pin "76") (pinfunction "PB15_76") (pintype "bidirectional"))
    )
    (net (code "82") (name "unconnected-(U1-PC1-Pad27)") (class "Default")
      (node (ref "U1") (pin "27") (pinfunction "PC1_27") (pintype "bidirectional"))
    )
    (net (code "83") (name "unconnected-(U1-PC2-Pad28)") (class "Default")
      (node (ref "U1") (pin "28") (pinfunction "PC2_28") (pintype "bidirectional"))
    )
    (net (code "84") (name "unconnected-(U1-PC3-Pad29)") (class "Default")
      (node (ref "U1") (pin "29") (pinfunction "PC3_29") (pintype "bidirectional"))
    )
    (net (code "85") (name "unconnected-(U1-PC4-Pad44)") (class "Default")
      (node (ref "U1") (pin "44") (pinfunction "PC4_44") (pintype "bidirectional"))
    )
    (net (code "86") (name "unconnected-(U1-PC5-Pad45)") (class "Default")
      (node (ref "U1") (pin "45") (pinfunction "PC5_45") (pintype "bidirectional"))
    )
    (net (code "87") (name "unconnected-(U1-PC6-Pad96)") (class "Default")
      (node (ref "U1") (pin "96") (pinfunction "PC6_96") (pintype "bidirectional"))
    )
    (net (code "88") (name "unconnected-(U1-PC7-Pad97)") (class "Default")
      (node (ref "U1") (pin "97") (pinfunction "PC7_97") (pintype "bidirectional"))
    )
    (net (code "89") (name "unconnected-(U1-PC8-Pad98)") (class "Default")
      (node (ref "U1") (pin "98") (pinfunction "PC8_98") (pintype "bidirectional"))
    )
    (net (code "90") (name "unconnected-(U1-PC9-Pad99)") (class "Default")
      (node (ref "U1") (pin "99") (pinfunction "PC9_99") (pintype "bidirectional"))
    )
    (net (code "91") (name "unconnected-(U1-PC10-Pad111)") (class "Default")
      (node (ref "U1") (pin "111") (pinfunction "PC10_111") (pintype "bidirectional"))
    )
    (net (code "92") (name "unconnected-(U1-PC11-Pad112)") (class "Default")
      (node (ref "U1") (pin "112") (pinfunction "PC11_112") (pintype "bidirectional"))
    )
    (net (code "93") (name "unconnected-(U1-PC12-Pad113)") (class "Default")
      (node (ref "U1") (pin "113") (pinfunction "PC12_113") (pintype "bidirectional"))
    )
    (net (code "94") (name "unconnected-(U1-PD0-Pad114)") (class "Default")
      (node (ref "U1") (pin "114") (pinfunction "PD0_114") (pintype "bidirectional"))
    )
    (net (code "95") (name "unconnected-(U1-PD1-Pad115)") (class "Default")
      (node (ref "U1") (pin "115") (pinfunction "PD1_115") (pintype "bidirectional"))
    )
    (net (code "96") (name "unconnected-(U1-PD2-Pad116)") (class "Default")
      (node (ref "U1") (pin "116") (pinfunction "PD2_116") (pintype "bidirectional"))
    )
    (net (code "97") (name "unconnected-(U1-PD3-Pad117)") (class "Default")
      (node (ref "U1") (pin "117") (pinfunction "PD3_117") (pintype "bidirectional"))
    )
    (net (code "98") (name "unconnected-(U1-PD4-Pad118)") (class "Default")
      (node (ref "U1") (pin "118") (pinfunction "PD4_118") (pintype "bidirectional"))
    )
    (net (code "99") (name "unconnected-(U1-PD5-Pad119)") (class "Default")
      (node (ref "U1") (pin "119") (pinfunction "PD5_119") (pintype "bidirectional"))
    )
    (net (code "100") (name "unconnected-(U1-PD6-Pad122)") (class "Default")
      (node (ref "U1") (pin "122") (pinfunction "PD6_122") (pintype "bidirectional"))
    )
    (net (code "101") (name "unconnected-(U1-PD7-Pad123)") (class "Default")
      (node (ref "U1") (pin "123") (pinfunction "PD7_123") (pintype "bidirectional"))
    )
    (net (code "102") (name "unconnected-(U1-PD10-Pad79)") (class "Default")
      (node (ref "U1") (pin "79") (pinfunction "PD10_79") (pintype "bidirectional"))
    )
    (net (code "103") (name "unconnected-(U1-PD11-Pad80)") (class "Default")
      (node (ref "U1") (pin "80") (pinfunction "PD11_80") (pintype "bidirectional"))
    )
    (net (code "104") (name "unconnected-(U1-PD12-Pad81)") (class "Default")
      (node (ref "U1") (pin "81") (pinfunction "PD12_81") (pintype "bidirectional"))
    )
    (net (code "105") (name "unconnected-(U1-PD13-Pad82)") (class "Default")
      (node (ref "U1") (pin "82") (pinfunction "PD13_82") (pintype "bidirectional"))
    )
    (net (code "106") (name "unconnected-(U1-PDR_ON-Pad143)") (class "Default")
      (node (ref "U1") (pin "143") (pinfunction "PDR_ON_143") (pintype "bidirectional"))
    )
    (net (code "107") (name "unconnected-(U1-PE2-Pad1)") (class "Default")
      (node (ref "U1") (pin "1") (pinfunction "PE2_1") (pintype "bidirectional"))
    )
    (net (code "108") (name "unconnected-(U1-PE3-Pad2)") (class "Default")
      (node (ref "U1") (pin "2") (pinfunction "PE3_2") (pintype "bidirectional"))
    )
    (net (code "109") (name "unconnected-(U1-PE4-Pad3)") (class "Default")
      (node (ref "U1") (pin "3") (pinfunction "PE4_3") (pintype "bidirectional"))
    )
    (net (code "110") (name "unconnected-(U1-PE5-Pad4)") (class "Default")
      (node (ref "U1") (pin "4") (pinfunction "PE5_4") (pintype "bidirectional"))
    )
    (net (code "111") (name "unconnected-(U1-PE6-Pad5)") (class "Default")
      (node (ref "U1") (pin "5") (pinfunction "PE6_5") (pintype "bidirectional"))
    )
    (net (code "112") (name "unconnected-(U1-PE7-Pad58)") (class "Default")
      (node (ref "U1") (pin "58") (pinfunction "PE7_58") (pintype "bidirectional"))
    )
    (net (code "113") (name "unconnected-(U1-PE8-Pad59)") (class "Default")
      (node (ref "U1") (pin "59") (pinfunction "PE8_59") (pintype "bidirectional"))
    )
    (net (code "114") (name "unconnected-(U1-PE10-Pad63)") (class "Default")
      (node (ref "U1") (pin "63") (pinfunction "PE10_63") (pintype "bidirectional"))
    )
    (net (code "115") (name "unconnected-(U1-PE12-Pad65)") (class "Default")
      (node (ref "U1") (pin "65") (pinfunction "PE12_65") (pintype "bidirectional"))
    )
    (net (code "116") (name "unconnected-(U1-PE14-Pad67)") (class "Default")
      (node (ref "U1") (pin "67") (pinfunction "PE14_67") (pintype "bidirectional"))
    )
    (net (code "117") (name "unconnected-(U1-PE15-Pad68)") (class "Default")
      (node (ref "U1") (pin "68") (pinfunction "PE15_68") (pintype "bidirectional"))
    )
    (net (code "118") (name "unconnected-(U1-PF0-Pad10)") (class "Default")
      (node (ref "U1") (pin "10") (pinfunction "PF0_10") (pintype "bidirectional"))
    )
    (net (code "119") (name "unconnected-(U1-PF1-Pad11)") (class "Default")
      (node (ref "U1") (pin "11") (pinfunction "PF1_11") (pintype "bidirectional"))
    )
    (net (code "120") (name "unconnected-(U1-PF2-Pad12)") (class "Default")
      (node (ref "U1") (pin "12") (pinfunction "PF2_12") (pintype "bidirectional"))
    )
    (net (code "121") (name "unconnected-(U1-PF3-Pad13)") (class "Default")
      (node (ref "U1") (pin "13") (pinfunction "PF3_13") (pintype "bidirectional"))
    )
    (net (code "122") (name "unconnected-(U1-PF4-Pad14)") (class "Default")
      (node (ref "U1") (pin "14") (pinfunction "PF4_14") (pintype "bidirectional"))
    )
    (net (code "123") (name "unconnected-(U1-PF5-Pad15)") (class "Default")
      (node (ref "U1") (pin "15") (pinfunction "PF5_15") (pintype "bidirectional"))
    )
    (net (code "124") (name "unconnected-(U1-PF6-Pad18)") (class "Default")
      (node (ref "U1") (pin "18") (pinfunction "PF6_18") (pintype "bidirectional"))
    )
    (net (code "125") (name "unconnected-(U1-PF7-Pad19)") (class "Default")
      (node (ref "U1") (pin "19") (pinfunction "PF7_19") (pintype "bidirectional"))
    )
    (net (code "126") (name "unconnected-(U1-PF8-Pad20)") (class "Default")
      (node (ref "U1") (pin "20") (pinfunction "PF8_20") (pintype "bidirectional"))
    )
    (net (code "127") (name "unconnected-(U1-PF9-Pad21)") (class "Default")
      (node (ref "U1") (pin "21") (pinfunction "PF9_21") (pintype "bidirectional"))
    )
    (net (code "128") (name "unconnected-(U1-PF10-Pad22)") (class "Default")
      (node (ref "U1") (pin "22") (pinfunction "PF10_22") (pintype "bidirectional"))
    )
    (net (code "129") (name "unconnected-(U1-PF11-Pad49)") (class "Default")
      (node (ref "U1") (pin "49") (pinfunction "PF11_49") (pintype "bidirectional"))
    )
    (net (code "130") (name "unconnected-(U1-PG0-Pad56)") (class "Default")
      (node (ref "U1") (pin "56") (pinfunction "PG0_56") (pintype "bidirectional"))
    )
    (net (code "131") (name "unconnected-(U1-PG1-Pad57)") (class "Default")
      (node (ref "U1") (pin "57") (pinfunction "PG1_57") (pintype "bidirectional"))
    )
    (net (code "132") (name "unconnected-(U1-PG2-Pad87)") (class "Default")
      (node (ref "U1") (pin "87") (pinfunction "PG2_87") (pintype "bidirectional"))
    )
    (net (code "133") (name "unconnected-(U1-PG3-Pad88)") (class "Default")
      (node (ref "U1") (pin "88") (pinfunction "PG3_88") (pintype "bidirectional"))
    )
    (net (code "134") (name "unconnected-(U1-PG4-Pad89)") (class "Default")
      (node (ref "U1") (pin "89") (pinfunction "PG4_89") (pintype "bidirectional"))
    )
    (net (code "135") (name "unconnected-(U1-PG5-Pad90)") (class "Default")
      (node (ref "U1") (pin "90") (pinfunction "PG5_90") (pintype "bidirectional"))
    )
    (net (code "136") (name "unconnected-(U1-PG6-Pad91)") (class "Default")
      (node (ref "U1") (pin "91") (pinfunction "PG6_91") (pintype "bidirectional"))
    )
    (net (code "137") (name "unconnected-(U1-PG7-Pad92)") (class "Default")
      (node (ref "U1") (pin "92") (pinfunction "PG7_92") (pintype "bidirectional"))
    )
    (net (code "138") (name "unconnected-(U1-PG8-Pad93)") (class "Default")
      (node (ref "U1") (pin "93") (pinfunction "PG8_93") (pintype "bidirectional"))
    )
    (net (code "139") (name "unconnected-(U1-PG10-Pad125)") (class "Default")
      (node (ref "U1") (pin "125") (pinfunction "PG10_125") (pintype "bidirectional"))
    )
    (net (code "140") (name "unconnected-(U1-PG11-Pad126)") (class "Default")
      (node (ref "U1") (pin "126") (pinfunction "PG11_126") (pintype "bidirectional"))
    )
    (net (code "141") (name "unconnected-(U1-PG12-Pad127)") (class "Default")
      (node (ref "U1") (pin "127") (pinfunction "PG12_127") (pintype "bidirectional"))
    )
    (net (code "142") (name "unconnected-(U1-PG13-Pad128)") (class "Default")
      (node (ref "U1") (pin "128") (pinfunction "PG13_128") (pintype "bidirectional"))
    )
    (net (code "143") (name "unconnected-(U1-PG15-Pad132)") (class "Default")
      (node (ref "U1") (pin "132") (pinfunction "PG15_132") (pintype "bidirectional"))
    )
    (net (code "144") (name "unconnected-(U2-NC-Pad5)") (class "Default")
      (node (ref "U2") (pin "5") (pinfunction "NC_5") (pintype "no_connect"))
    )
    (net (code "145") (name "unconnected-(U2-PG-Pad3)") (class "Default")
      (node (ref "U2") (pin "3") (pinfunction "PG_3") (pintype "bidirectional"))
    )
    (net (code "146") (name "unconnected-(U5-NC-Pad3)") (class "Default")
      (node (ref "U5") (pin "3") (pinfunction "NC_3") (pintype "no_connect"))
    )
    (net (code "147") (name "unconnected-(U5-NC2-Pad6)") (class "Default")
      (node (ref "U5") (pin "6") (pinfunction "NC2_6") (pintype "no_connect"))
    )
    (net (code "148") (name "unconnected-(U5-NC3-Pad8)") (class "Default")
      (node (ref "U5") (pin "8") (pinfunction "NC3_8") (pintype "no_connect"))
    )
  )
)
